# 09-I225-2.net
KiCad netlist of a schematic drawn in Altium Designer
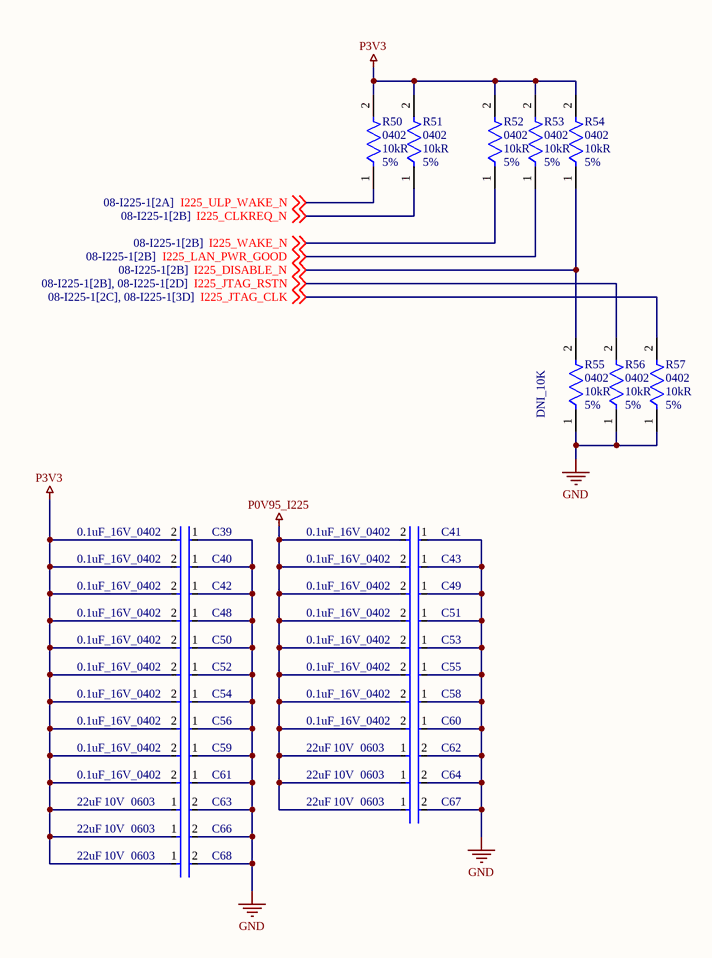
[diagram p0: 09-I225-2.SchDoc]

(export (version "E")
  (design (tool "Eeschema 10.0.6"))
  (components
    (comp (ref "C39")
      (value "0.1uF_16V_0402")
      (footprint "FP-GRM15-MFG")
      (description "CAP CER 0.1UF 16V X7R 0402")
      (fields (field (name "MANUFACTURER PART NUMBER") "GRM155R71C104KA88D") (field (name "TOLERANCE") "10%"))
      (libsource (lib "Altium Content Vault") (part "236180d848d6139a670b325ea6854c9"))
    )
    (comp (ref "C40")
      (value "0.1uF_16V_0402")
      (footprint "FP-GRM15-MFG")
      (description "CAP CER 0.1UF 16V X7R 0402")
      (fields (field (name "MANUFACTURER PART NUMBER") "GRM155R71C104KA88D") (field (name "TOLERANCE") "10%"))
      (libsource (lib "Altium Content Vault") (part "236180d848d6139a670b325ea6854c9"))
    )
    (comp (ref "C41")
      (value "0.1uF_16V_0402")
      (footprint "FP-GRM15-MFG")
      (description "CAP CER 0.1UF 16V X7R 0402")
      (fields (field (name "MANUFACTURER PART NUMBER") "GRM155R71C104KA88D") (field (name "TOLERANCE") "10%"))
      (libsource (lib "Altium Content Vault") (part "236180d848d6139a670b325ea6854c9"))
    )
    (comp (ref "C42")
      (value "0.1uF_16V_0402")
      (footprint "FP-GRM15-MFG")
      (description "CAP CER 0.1UF 16V X7R 0402")
      (fields (field (name "MANUFACTURER PART NUMBER") "GRM155R71C104KA88D") (field (name "TOLERANCE") "10%"))
      (libsource (lib "Altium Content Vault") (part "236180d848d6139a670b325ea6854c9"))
    )
    (comp (ref "C43")
      (value "0.1uF_16V_0402")
      (footprint "FP-GRM15-MFG")
      (description "CAP CER 0.1UF 16V X7R 0402")
      (fields (field (name "MANUFACTURER PART NUMBER") "GRM155R71C104KA88D") (field (name "TOLERANCE") "10%"))
      (libsource (lib "Altium Content Vault") (part "236180d848d6139a670b325ea6854c9"))
    )
    (comp (ref "C48")
      (value "0.1uF_16V_0402")
      (footprint "FP-GRM15-MFG")
      (description "CAP CER 0.1UF 16V X7R 0402")
      (fields (field (name "MANUFACTURER PART NUMBER") "GRM155R71C104KA88D") (field (name "TOLERANCE") "10%"))
      (libsource (lib "Altium Content Vault") (part "236180d848d6139a670b325ea6854c9"))
    )
    (comp (ref "C49")
      (value "0.1uF_16V_0402")
      (footprint "FP-GRM15-MFG")
      (description "CAP CER 0.1UF 16V X7R 0402")
      (fields (field (name "MANUFACTURER PART NUMBER") "GRM155R71C104KA88D") (field (name "TOLERANCE") "10%"))
      (libsource (lib "Altium Content Vault") (part "236180d848d6139a670b325ea6854c9"))
    )
    (comp (ref "C50")
      (value "0.1uF_16V_0402")
      (footprint "FP-GRM15-MFG")
      (description "CAP CER 0.1UF 16V X7R 0402")
      (fields (field (name "MANUFACTURER PART NUMBER") "GRM155R71C104KA88D") (field (name "TOLERANCE") "10%"))
      (libsource (lib "Altium Content Vault") (part "236180d848d6139a670b325ea6854c9"))
    )
    (comp (ref "C51")
      (value "0.1uF_16V_0402")
      (footprint "FP-GRM15-MFG")
      (description "CAP CER 0.1UF 16V X7R 0402")
      (fields (field (name "MANUFACTURER PART NUMBER") "GRM155R71C104KA88D") (field (name "TOLERANCE") "10%"))
      (libsource (lib "Altium Content Vault") (part "236180d848d6139a670b325ea6854c9"))
    )
    (comp (ref "C52")
      (value "0.1uF_16V_0402")
      (footprint "FP-GRM15-MFG")
      (description "CAP CER 0.1UF 16V X7R 0402")
      (fields (field (name "MANUFACTURER PART NUMBER") "GRM155R71C104KA88D") (field (name "TOLERANCE") "10%"))
      (libsource (lib "Altium Content Vault") (part "236180d848d6139a670b325ea6854c9"))
    )
    (comp (ref "C53")
      (value "0.1uF_16V_0402")
      (footprint "FP-GRM15-MFG")
      (description "CAP CER 0.1UF 16V X7R 0402")
      (fields (field (name "MANUFACTURER PART NUMBER") "GRM155R71C104KA88D") (field (name "TOLERANCE") "10%"))
      (libsource (lib "Altium Content Vault") (part "236180d848d6139a670b325ea6854c9"))
    )
    (comp (ref "C54")
      (value "0.1uF_16V_0402")
      (footprint "FP-GRM15-MFG")
      (description "CAP CER 0.1UF 16V X7R 0402")
      (fields (field (name "MANUFACTURER PART NUMBER") "GRM155R71C104KA88D") (field (name "TOLERANCE") "10%"))
      (libsource (lib "Altium Content Vault") (part "236180d848d6139a670b325ea6854c9"))
    )
    (comp (ref "C55")
      (value "0.1uF_16V_0402")
      (footprint "FP-GRM15-MFG")
      (description "CAP CER 0.1UF 16V X7R 0402")
      (fields (field (name "MANUFACTURER PART NUMBER") "GRM155R71C104KA88D") (field (name "TOLERANCE") "10%"))
      (libsource (lib "Altium Content Vault") (part "236180d848d6139a670b325ea6854c9"))
    )
    (comp (ref "C56")
      (value "0.1uF_16V_0402")
      (footprint "FP-GRM15-MFG")
      (description "CAP CER 0.1UF 16V X7R 0402")
      (fields (field (name "MANUFACTURER PART NUMBER") "GRM155R71C104KA88D") (field (name "TOLERANCE") "10%"))
      (libsource (lib "Altium Content Vault") (part "236180d848d6139a670b325ea6854c9"))
    )
    (comp (ref "C58")
      (value "0.1uF_16V_0402")
      (footprint "FP-GRM15-MFG")
      (description "CAP CER 0.1UF 16V X7R 0402")
      (fields (field (name "MANUFACTURER PART NUMBER") "GRM155R71C104KA88D") (field (name "TOLERANCE") "10%"))
      (libsource (lib "Altium Content Vault") (part "236180d848d6139a670b325ea6854c9"))
    )
    (comp (ref "C59")
      (value "0.1uF_16V_0402")
      (footprint "FP-GRM15-MFG")
      (description "CAP CER 0.1UF 16V X7R 0402")
      (fields (field (name "MANUFACTURER PART NUMBER") "GRM155R71C104KA88D") (field (name "TOLERANCE") "10%"))
      (libsource (lib "Altium Content Vault") (part "236180d848d6139a670b325ea6854c9"))
    )
    (comp (ref "C60")
      (value "0.1uF_16V_0402")
      (footprint "FP-GRM15-MFG")
      (description "CAP CER 0.1UF 16V X7R 0402")
      (fields (field (name "MANUFACTURER PART NUMBER") "GRM155R71C104KA88D") (field (name "TOLERANCE") "10%"))
      (libsource (lib "Altium Content Vault") (part "236180d848d6139a670b325ea6854c9"))
    )
    (comp (ref "C61")
      (value "0.1uF_16V_0402")
      (footprint "FP-GRM15-MFG")
      (description "CAP CER 0.1UF 16V X7R 0402")
      (fields (field (name "MANUFACTURER PART NUMBER") "GRM155R71C104KA88D") (field (name "TOLERANCE") "10%"))
      (libsource (lib "Altium Content Vault") (part "236180d848d6139a670b325ea6854c9"))
    )
    (comp (ref "C62")
      (value "GRM188R61A226ME15D")
      (footprint "FP-GRM188-0_2-IPC_C")
      (description "Chip Multilayer Ceramic Capacitors for General Purpose, 0603, 22uF, X5R, 15%, 20%, 10V")
      (fields
        (field (name "TOLERANCE") "20%")
        (field (name "CAPACITANCE") "22uF")
        (field (name "VOLTAGE RATING") "10V")
        (field (name "CASE CODE (IMPERIAL)") "0603")
      )
      (libsource (lib "Altium Content Vault") (part "11868f565c42a9108669ba33697ecf6"))
    )
    (comp (ref "C63")
      (value "GRM188R61A226ME15D")
      (footprint "FP-GRM188-0_2-IPC_C")
      (description "Chip Multilayer Ceramic Capacitors for General Purpose, 0603, 22uF, X5R, 15%, 20%, 10V")
      (fields
        (field (name "TOLERANCE") "20%")
        (field (name "CAPACITANCE") "22uF")
        (field (name "VOLTAGE RATING") "10V")
        (field (name "CASE CODE (IMPERIAL)") "0603")
      )
      (libsource (lib "Altium Content Vault") (part "11868f565c42a9108669ba33697ecf6"))
    )
    (comp (ref "C64")
      (value "GRM188R61A226ME15D")
      (footprint "FP-GRM188-0_2-IPC_C")
      (description "Chip Multilayer Ceramic Capacitors for General Purpose, 0603, 22uF, X5R, 15%, 20%, 10V")
      (fields
        (field (name "TOLERANCE") "20%")
        (field (name "CAPACITANCE") "22uF")
        (field (name "VOLTAGE RATING") "10V")
        (field (name "CASE CODE (IMPERIAL)") "0603")
      )
      (libsource (lib "Altium Content Vault") (part "11868f565c42a9108669ba33697ecf6"))
    )
    (comp (ref "C66")
      (value "GRM188R61A226ME15D")
      (footprint "FP-GRM188-0_2-IPC_C")
      (description "Chip Multilayer Ceramic Capacitors for General Purpose, 0603, 22uF, X5R, 15%, 20%, 10V")
      (fields
        (field (name "TOLERANCE") "20%")
        (field (name "CAPACITANCE") "22uF")
        (field (name "VOLTAGE RATING") "10V")
        (field (name "CASE CODE (IMPERIAL)") "0603")
      )
      (libsource (lib "Altium Content Vault") (part "11868f565c42a9108669ba33697ecf6"))
    )
    (comp (ref "C67")
      (value "GRM188R61A226ME15D")
      (footprint "FP-GRM188-0_2-IPC_C")
      (description "Chip Multilayer Ceramic Capacitors for General Purpose, 0603, 22uF, X5R, 15%, 20%, 10V")
      (fields
        (field (name "TOLERANCE") "20%")
        (field (name "CAPACITANCE") "22uF")
        (field (name "VOLTAGE RATING") "10V")
        (field (name "CASE CODE (IMPERIAL)") "0603")
      )
      (libsource (lib "Altium Content Vault") (part "11868f565c42a9108669ba33697ecf6"))
    )
    (comp (ref "C68")
      (value "GRM188R61A226ME15D")
      (footprint "FP-GRM188-0_2-IPC_C")
      (description "Chip Multilayer Ceramic Capacitors for General Purpose, 0603, 22uF, X5R, 15%, 20%, 10V")
      (fields
        (field (name "TOLERANCE") "20%")
        (field (name "CAPACITANCE") "22uF")
        (field (name "VOLTAGE RATING") "10V")
        (field (name "CASE CODE (IMPERIAL)") "0603")
      )
      (libsource (lib "Altium Content Vault") (part "11868f565c42a9108669ba33697ecf6"))
    )
    (comp (ref "R50")
      (value "CRCW040210K0JNED")
      (footprint "FP-CRCW0402-e3-IPC_B")
      (description "RES Thick Film, 10kΩ, 5%, 0.063W, 200ppm/°C, 0402")
      (fields
        (field (name "CASE/PACKAGE") "0402")
        (field (name "RESISTANCE") "10kR")
        (field (name "TOLERANCE") "5%")
      )
      (libsource (lib "Altium Content Vault") (part "1029c3af85768c4190bb7ad29bc67b5"))
    )
    (comp (ref "R51")
      (value "CRCW040210K0JNED")
      (footprint "FP-CRCW0402-e3-IPC_B")
      (description "RES Thick Film, 10kΩ, 5%, 0.063W, 200ppm/°C, 0402")
      (fields
        (field (name "CASE/PACKAGE") "0402")
        (field (name "RESISTANCE") "10kR")
        (field (name "TOLERANCE") "5%")
      )
      (libsource (lib "Altium Content Vault") (part "1029c3af85768c4190bb7ad29bc67b5"))
    )
    (comp (ref "R52")
      (value "CRCW040210K0JNED")
      (footprint "FP-CRCW0402-e3-IPC_B")
      (description "RES Thick Film, 10kΩ, 5%, 0.063W, 200ppm/°C, 0402")
      (fields
        (field (name "CASE/PACKAGE") "0402")
        (field (name "RESISTANCE") "10kR")
        (field (name "TOLERANCE") "5%")
      )
      (libsource (lib "Altium Content Vault") (part "1029c3af85768c4190bb7ad29bc67b5"))
    )
    (comp (ref "R53")
      (value "CRCW040210K0JNED")
      (footprint "FP-CRCW0402-e3-IPC_B")
      (description "RES Thick Film, 10kΩ, 5%, 0.063W, 200ppm/°C, 0402")
      (fields
        (field (name "CASE/PACKAGE") "0402")
        (field (name "RESISTANCE") "10kR")
        (field (name "TOLERANCE") "5%")
      )
      (libsource (lib "Altium Content Vault") (part "1029c3af85768c4190bb7ad29bc67b5"))
    )
    (comp (ref "R54")
      (value "CRCW040210K0JNED")
      (footprint "FP-CRCW0402-e3-IPC_B")
      (description "RES Thick Film, 10kΩ, 5%, 0.063W, 200ppm/°C, 0402")
      (fields
        (field (name "CASE/PACKAGE") "0402")
        (field (name "RESISTANCE") "10kR")
        (field (name "TOLERANCE") "5%")
      )
      (libsource (lib "Altium Content Vault") (part "1029c3af85768c4190bb7ad29bc67b5"))
    )
    (comp (ref "R55")
      (value "DNI_10K")
      (footprint "FP-CRCW0402-e3-IPC_B")
      (description "RES Thick Film, 10kΩ, 5%, 0.063W, 200ppm/°C, 0402")
      (fields
        (field (name "CASE/PACKAGE") "0402")
        (field (name "RESISTANCE") "10kR")
        (field (name "TOLERANCE") "5%")
      )
      (libsource (lib "Altium Content Vault") (part "1029c3af85768c4190bb7ad29bc67b5"))
    )
    (comp (ref "R56")
      (value "CRCW040210K0JNED")
      (footprint "FP-CRCW0402-e3-IPC_B")
      (description "RES Thick Film, 10kΩ, 5%, 0.063W, 200ppm/°C, 0402")
      (fields
        (field (name "CASE/PACKAGE") "0402")
        (field (name "RESISTANCE") "10kR")
        (field (name "TOLERANCE") "5%")
      )
      (libsource (lib "Altium Content Vault") (part "1029c3af85768c4190bb7ad29bc67b5"))
    )
    (comp (ref "R57")
      (value "CRCW040210K0JNED")
      (footprint "FP-CRCW0402-e3-IPC_B")
      (description "RES Thick Film, 10kΩ, 5%, 0.063W, 200ppm/°C, 0402")
      (fields
        (field (name "CASE/PACKAGE") "0402")
        (field (name "RESISTANCE") "10kR")
        (field (name "TOLERANCE") "5%")
      )
      (libsource (lib "Altium Content Vault") (part "1029c3af85768c4190bb7ad29bc67b5"))
    )
  )
  (nets
    (net (code "1") (name "GND") (class "Default")
      (node (ref "C39") (pin "1") (pinfunction "1_1") (pintype "passive"))
      (node (ref "C40") (pin "1") (pinfunction "1_1") (pintype "passive"))
      (node (ref "C41") (pin "1") (pinfunction "1_1") (pintype "passive"))
      (node (ref "C42") (pin "1") (pinfunction "1_1") (pintype "passive"))
      (node (ref "C43") (pin "1") (pinfunction "1_1") (pintype "passive"))
      (node (ref "C48") (pin "1") (pinfunction "1_1") (pintype "passive"))
      (node (ref "C49") (pin "1") (pinfunction "1_1") (pintype "passive"))
      (node (ref "C50") (pin "1") (pinfunction "1_1") (pintype "passive"))
      (node (ref "C51") (pin "1") (pinfunction "1_1") (pintype "passive"))
      (node (ref "C52") (pin "1") (pinfunction "1_1") (pintype "passive"))
      (node (ref "C53") (pin "1") (pinfunction "1_1") (pintype "passive"))
      (node (ref "C54") (pin "1") (pinfunction "1_1") (pintype "passive"))
      (node (ref "C55") (pin "1") (pinfunction "1_1") (pintype "passive"))
      (node (ref "C56") (pin "1") (pinfunction "1_1") (pintype "passive"))
      (node (ref "C58") (pin "1") (pinfunction "1_1") (pintype "passive"))
      (node (ref "C59") (pin "1") (pinfunction "1_1") (pintype "passive"))
      (node (ref "C60") (pin "1") (pinfunction "1_1") (pintype "passive"))
      (node (ref "C61") (pin "1") (pinfunction "1_1") (pintype "passive"))
      (node (ref "C62") (pin "2") (pinfunction "2_2") (pintype "passive"))
      (node (ref "C63") (pin "2") (pinfunction "2_2") (pintype "passive"))
      (node (ref "C64") (pin "2") (pinfunction "2_2") (pintype "passive"))
      (node (ref "C66") (pin "2") (pinfunction "2_2") (pintype "passive"))
      (node (ref "C67") (pin "2") (pinfunction "2_2") (pintype "passive"))
      (node (ref "C68") (pin "2") (pinfunction "2_2") (pintype "passive"))
      (node (ref "R55") (pin "1") (pinfunction "1_1") (pintype "passive"))
      (node (ref "R56") (pin "1") (pinfunction "1_1") (pintype "passive"))
      (node (ref "R57") (pin "1") (pinfunction "1_1") (pintype "passive"))
    )
    (net (code "2") (name "I225_CLKREQ_N") (class "Default")
      (node (ref "R51") (pin "1") (pinfunction "1_1") (pintype "passive"))
    )
    (net (code "3") (name "I225_DISABLE_N") (class "Default")
      (node (ref "R54") (pin "1") (pinfunction "1_1") (pintype "passive"))
      (node (ref "R55") (pin "2") (pinfunction "2_2") (pintype "passive"))
    )
    (net (code "4") (name "I225_JTAG_CLK") (class "Default")
      (node (ref "R57") (pin "2") (pinfunction "2_2") (pintype "passive"))
    )
    (net (code "5") (name "I225_JTAG_RSTN") (class "Default")
      (node (ref "R56") (pin "2") (pinfunction "2_2") (pintype "passive"))
    )
    (net (code "6") (name "I225_LAN_PWR_GOOD") (class "Default")
      (node (ref "R53") (pin "1") (pinfunction "1_1") (pintype "passive"))
    )
    (net (code "7") (name "I225_ULP_WAKE_N") (class "Default")
      (node (ref "R50") (pin "1") (pinfunction "1_1") (pintype "passive"))
    )
    (net (code "8") (name "I225_WAKE_N") (class "Default")
      (node (ref "R52") (pin "1") (pinfunction "1_1") (pintype "passive"))
    )
    (net (code "9") (name "P0V95_I225") (class "Default")
      (node (ref "C41") (pin "2") (pinfunction "2_2") (pintype "passive"))
      (node (ref "C43") (pin "2") (pinfunction "2_2") (pintype "passive"))
      (node (ref "C49") (pin "2") (pinfunction "2_2") (pintype "passive"))
      (node (ref "C51") (pin "2") (pinfunction "2_2") (pintype "passive"))
      (node (ref "C53") (pin "2") (pinfunction "2_2") (pintype "passive"))
      (node (ref "C55") (pin "2") (pinfunction "2_2") (pintype "passive"))
      (node (ref "C58") (pin "2") (pinfunction "2_2") (pintype "passive"))
      (node (ref "C60") (pin "2") (pinfunction "2_2") (pintype "passive"))
      (node (ref "C62") (pin "1") (pinfunction "1_1") (pintype "passive"))
      (node (ref "C64") (pin "1") (pinfunction "1_1") (pintype "passive"))
      (node (ref "C67") (pin "1") (pinfunction "1_1") (pintype "passive"))
    )
    (net (code "10") (name "P3V3") (class "Default")
      (node (ref "C39") (pin "2") (pinfunction "2_2") (pintype "passive"))
      (node (ref "C40") (pin "2") (pinfunction "2_2") (pintype "passive"))
      (node (ref "C42") (pin "2") (pinfunction "2_2") (pintype "passive"))
      (node (ref "C48") (pin "2") (pinfunction "2_2") (pintype "passive"))
      (node (ref "C50") (pin "2") (pinfunction "2_2") (pintype "passive"))
      (node (ref "C52") (pin "2") (pinfunction "2_2") (pintype "passive"))
      (node (ref "C54") (pin "2") (pinfunction "2_2") (pintype "passive"))
      (node (ref "C56") (pin "2") (pinfunction "2_2") (pintype "passive"))
      (node (ref "C59") (pin "2") (pinfunction "2_2") (pintype "passive"))
      (node (ref "C61") (pin "2") (pinfunction "2_2") (pintype "passive"))
      (node (ref "C63") (pin "1") (pinfunction "1_1") (pintype "passive"))
      (node (ref "C66") (pin "1") (pinfunction "1_1") (pintype "passive"))
      (node (ref "C68") (pin "1") (pinfunction "1_1") (pintype "passive"))
      (node (ref "R50") (pin "2") (pinfunction "2_2") (pintype "passive"))
      (node (ref "R51") (pin "2") (pinfunction "2_2") (pintype "passive"))
      (node (ref "R52") (pin "2") (pinfunction "2_2") (pintype "passive"))
      (node (ref "R53") (pin "2") (pinfunction "2_2") (pintype "passive"))
      (node (ref "R54") (pin "2") (pinfunction "2_2") (pintype "passive"))
    )
  )
)
